# SH1_-_Connectors.net
KiCad netlist of a schematic drawn in Altium Designer
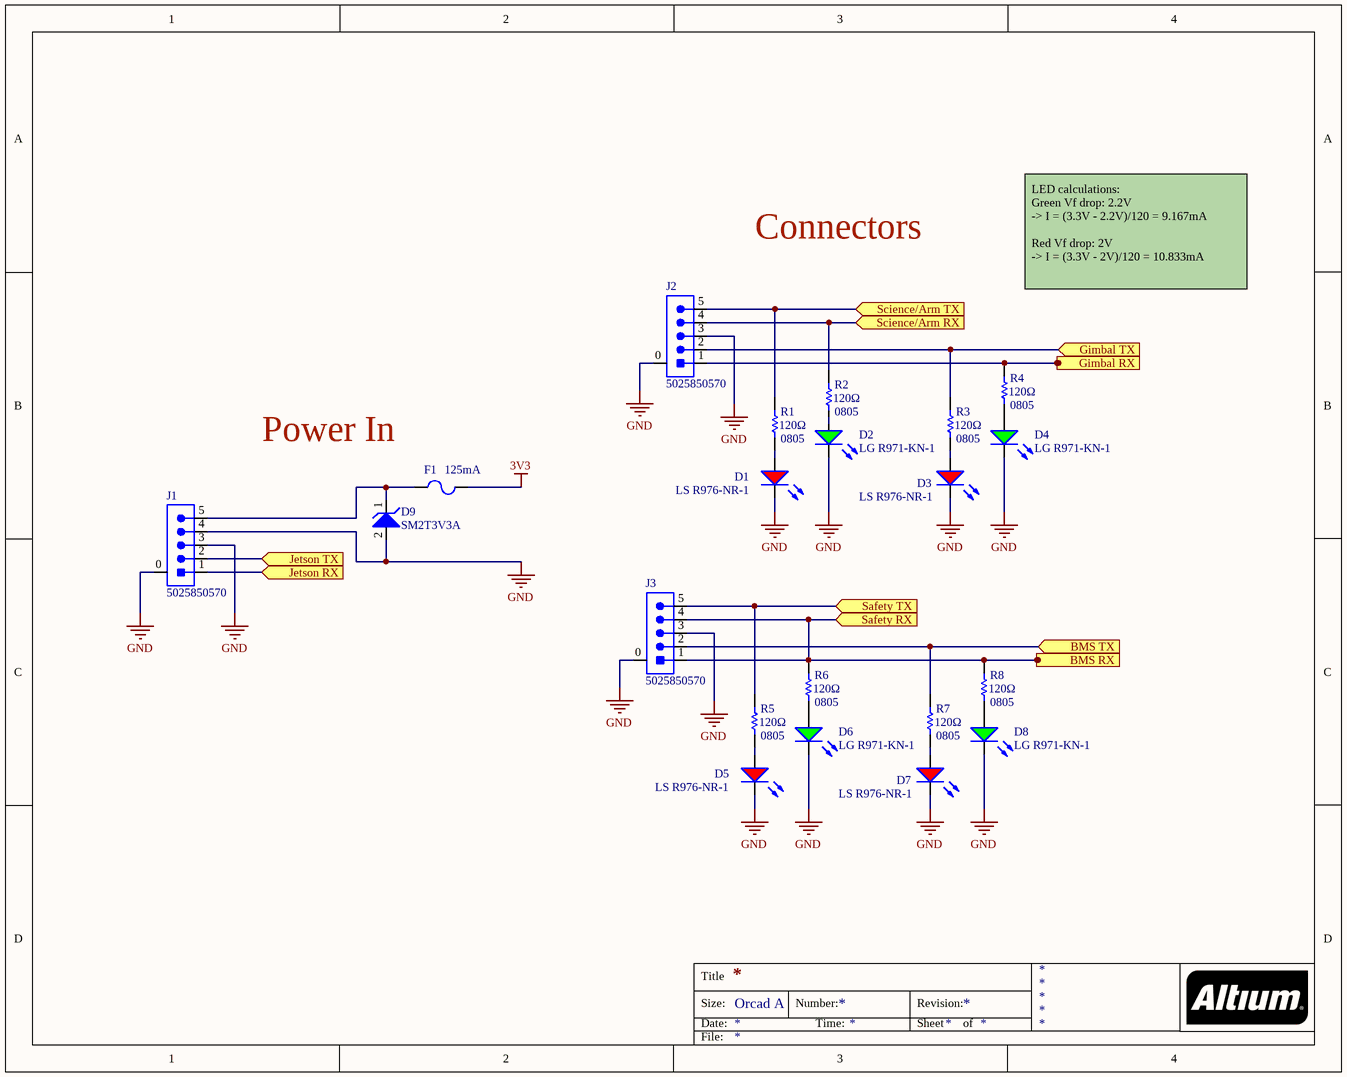
[diagram p0: SH1 - Connectors.SchDoc]

(export (version "E")
  (design (tool "Eeschema 10.0.6"))
  (components
    (comp (ref "D1")
      (value "LS R976-NR-1")
      (footprint "LED_0805_LINE")
      (description "LED RED DIFFUSED 0805 SMD")
      (fields (field (name "MANUFACTURER PART NUMBER 1") "LS R976-NR-1"))
      (libsource (lib "UWRT_Schematic_Library_2020") (part "DIO_LED_R"))
    )
    (comp (ref "D2")
      (value "LG R971-KN-1")
      (footprint "LED_0805_LINE")
      (description "LED GREEN DIFFUSED 0805 SMD")
      (fields (field (name "MANUFACTURER PART NUMBER 1") "LG R971-KN-1"))
      (libsource (lib "UWRT_Schematic_Library_2020") (part "DIO_LED_G"))
    )
    (comp (ref "D3")
      (value "LS R976-NR-1")
      (footprint "LED_0805_LINE")
      (description "LED RED DIFFUSED 0805 SMD")
      (fields (field (name "MANUFACTURER PART NUMBER 1") "LS R976-NR-1"))
      (libsource (lib "UWRT_Schematic_Library_2020") (part "DIO_LED_R"))
    )
    (comp (ref "D4")
      (value "LG R971-KN-1")
      (footprint "LED_0805_LINE")
      (description "LED GREEN DIFFUSED 0805 SMD")
      (fields (field (name "MANUFACTURER PART NUMBER 1") "LG R971-KN-1"))
      (libsource (lib "UWRT_Schematic_Library_2020") (part "DIO_LED_G"))
    )
    (comp (ref "D5")
      (value "LS R976-NR-1")
      (footprint "LED_0805_LINE")
      (description "LED RED DIFFUSED 0805 SMD")
      (fields (field (name "MANUFACTURER PART NUMBER 1") "LS R976-NR-1"))
      (libsource (lib "UWRT_Schematic_Library_2020") (part "DIO_LED_R"))
    )
    (comp (ref "D6")
      (value "LG R971-KN-1")
      (footprint "LED_0805_LINE")
      (description "LED GREEN DIFFUSED 0805 SMD")
      (fields (field (name "MANUFACTURER PART NUMBER 1") "LG R971-KN-1"))
      (libsource (lib "UWRT_Schematic_Library_2020") (part "DIO_LED_G"))
    )
    (comp (ref "D7")
      (value "LS R976-NR-1")
      (footprint "LED_0805_LINE")
      (description "LED RED DIFFUSED 0805 SMD")
      (fields (field (name "MANUFACTURER PART NUMBER 1") "LS R976-NR-1"))
      (libsource (lib "UWRT_Schematic_Library_2020") (part "DIO_LED_R"))
    )
    (comp (ref "D8")
      (value "LG R971-KN-1")
      (footprint "LED_0805_LINE")
      (description "LED GREEN DIFFUSED 0805 SMD")
      (fields (field (name "MANUFACTURER PART NUMBER 1") "LG R971-KN-1"))
      (libsource (lib "UWRT_Schematic_Library_2020") (part "DIO_LED_G"))
    )
    (comp (ref "D9")
      (value "TVS_DIODE_UNIDIR_3.3V")
      (footprint "TVS_DIODE_UNIDIR")
      (description "TVS DIODE 3.3V 6.8V DO216AA")
      (fields
        (field (name "MANUFACTURER") "STMicroelectronics")
        (field (name "MANUFACTURER PART NUMBER") "SM2T3V3A")
      )
      (libsource (lib "UWRT_Schematic_Library_2020") (part "TVS_DIODE_UNIDIR_3.3V"))
    )
    (comp (ref "F1")
      (value "FUSE_125mA_1206")
      (footprint "FUSE_1206")
      (description "FUSE SMD 125mA 125V")
      (fields (field (name "CURRENT RATING") "125mA"))
      (libsource (lib "UWRT_Schematic_Library_2020") (part "FUSE_125mA_1206"))
    )
    (comp (ref "J1")
      (value "CON_5M_SM_RA")
      (footprint "MOLEX-5025850570")
      (description "CONN HEADER SMD RIGHT ANGLE 1.5MM PITCH")
      (fields (field (name "MANUFACTURER PART NUMBER 1") "5025850570"))
      (libsource (lib "UWRT_Schematic_Library_2020") (part "CON_5M_SM_RA"))
    )
    (comp (ref "J2")
      (value "CON_5M_SM_RA")
      (footprint "MOLEX-5025850570")
      (description "CONN HEADER SMD RIGHT ANGLE 1.5MM PITCH")
      (fields (field (name "MANUFACTURER PART NUMBER 1") "5025850570"))
      (libsource (lib "UWRT_Schematic_Library_2020") (part "CON_5M_SM_RA"))
    )
    (comp (ref "J3")
      (value "CON_5M_SM_RA")
      (footprint "MOLEX-5025850570")
      (description "CONN HEADER SMD RIGHT ANGLE 1.5MM PITCH")
      (fields (field (name "MANUFACTURER PART NUMBER 1") "5025850570"))
      (libsource (lib "UWRT_Schematic_Library_2020") (part "CON_5M_SM_RA"))
    )
    (comp (ref "R1")
      (value "120")
      (footprint "RESC2012X60N")
      (description "RES SMD 120 OHM 1% 1/8W 0805")
      (fields (field (name "CASE CODE (IMPERIAL)") "0805") (field (name "RESISTANCE") "120Ω"))
      (libsource (lib "UWRT_Schematic_Library_2020") (part "RES_120Ω_0805"))
    )
    (comp (ref "R2")
      (value "120")
      (footprint "RESC2012X60N")
      (description "RES SMD 120 OHM 1% 1/8W 0805")
      (fields (field (name "CASE CODE (IMPERIAL)") "0805") (field (name "RESISTANCE") "120Ω"))
      (libsource (lib "UWRT_Schematic_Library_2020") (part "RES_120Ω_0805"))
    )
    (comp (ref "R3")
      (value "120")
      (footprint "RESC2012X60N")
      (description "RES SMD 120 OHM 1% 1/8W 0805")
      (fields (field (name "CASE CODE (IMPERIAL)") "0805") (field (name "RESISTANCE") "120Ω"))
      (libsource (lib "UWRT_Schematic_Library_2020") (part "RES_120Ω_0805"))
    )
    (comp (ref "R4")
      (value "120")
      (footprint "RESC2012X60N")
      (description "RES SMD 120 OHM 1% 1/8W 0805")
      (fields (field (name "CASE CODE (IMPERIAL)") "0805") (field (name "RESISTANCE") "120Ω"))
      (libsource (lib "UWRT_Schematic_Library_2020") (part "RES_120Ω_0805"))
    )
    (comp (ref "R5")
      (value "120")
      (footprint "RESC2012X60N")
      (description "RES SMD 120 OHM 1% 1/8W 0805")
      (fields (field (name "CASE CODE (IMPERIAL)") "0805") (field (name "RESISTANCE") "120Ω"))
      (libsource (lib "UWRT_Schematic_Library_2020") (part "RES_120Ω_0805"))
    )
    (comp (ref "R6")
      (value "120")
      (footprint "RESC2012X60N")
      (description "RES SMD 120 OHM 1% 1/8W 0805")
      (fields (field (name "CASE CODE (IMPERIAL)") "0805") (field (name "RESISTANCE") "120Ω"))
      (libsource (lib "UWRT_Schematic_Library_2020") (part "RES_120Ω_0805"))
    )
    (comp (ref "R7")
      (value "120")
      (footprint "RESC2012X60N")
      (description "RES SMD 120 OHM 1% 1/8W 0805")
      (fields (field (name "CASE CODE (IMPERIAL)") "0805") (field (name "RESISTANCE") "120Ω"))
      (libsource (lib "UWRT_Schematic_Library_2020") (part "RES_120Ω_0805"))
    )
    (comp (ref "R8")
      (value "120")
      (footprint "RESC2012X60N")
      (description "RES SMD 120 OHM 1% 1/8W 0805")
      (fields (field (name "CASE CODE (IMPERIAL)") "0805") (field (name "RESISTANCE") "120Ω"))
      (libsource (lib "UWRT_Schematic_Library_2020") (part "RES_120Ω_0805"))
    )
  )
  (nets
    (net (code "1") (name "/BMS RX") (class "Default")
      (node (ref "J3") (pin "1") (pinfunction "1_1") (pintype "passive"))
      (node (ref "J3") (pin "4") (pinfunction "4_4") (pintype "passive"))
      (node (ref "R6") (pin "1") (pinfunction "1_1") (pintype "passive"))
      (node (ref "R8") (pin "1") (pinfunction "1_1") (pintype "passive"))
    )
    (net (code "2") (name "/BMS TX") (class "Default")
      (node (ref "J3") (pin "2") (pinfunction "2_2") (pintype "passive"))
      (node (ref "R7") (pin "1") (pinfunction "1_1") (pintype "passive"))
    )
    (net (code "3") (name "/Gimbal RX") (class "Default")
      (node (ref "J2") (pin "1") (pinfunction "1_1") (pintype "passive"))
      (node (ref "R4") (pin "1") (pinfunction "1_1") (pintype "passive"))
    )
    (net (code "4") (name "/Gimbal TX") (class "Default")
      (node (ref "J2") (pin "2") (pinfunction "2_2") (pintype "passive"))
      (node (ref "R3") (pin "1") (pinfunction "1_1") (pintype "passive"))
    )
    (net (code "5") (name "/Jetson RX") (class "Default")
      (node (ref "J1") (pin "1") (pinfunction "1_1") (pintype "passive"))
    )
    (net (code "6") (name "/Jetson TX") (class "Default")
      (node (ref "J1") (pin "2") (pinfunction "2_2") (pintype "passive"))
    )
    (net (code "7") (name "/Safety TX") (class "Default")
      (node (ref "J3") (pin "5") (pinfunction "5_5") (pintype "passive"))
      (node (ref "R5") (pin "1") (pinfunction "1_1") (pintype "passive"))
    )
    (net (code "8") (name "/Science{slash}Arm RX") (class "Default")
      (node (ref "J2") (pin "4") (pinfunction "4_4") (pintype "passive"))
      (node (ref "R2") (pin "1") (pinfunction "1_1") (pintype "passive"))
    )
    (net (code "9") (name "/Science{slash}Arm TX") (class "Default")
      (node (ref "J2") (pin "5") (pinfunction "5_5") (pintype "passive"))
      (node (ref "R1") (pin "1") (pinfunction "1_1") (pintype "passive"))
    )
    (net (code "10") (name "3V3") (class "Default")
      (node (ref "F1") (pin "2") (pinfunction "2_2") (pintype "passive"))
    )
    (net (code "11") (name "GND") (class "Default")
      (node (ref "D1") (pin "2") (pinfunction "K_2") (pintype "passive"))
      (node (ref "D2") (pin "2") (pinfunction "K_2") (pintype "passive"))
      (node (ref "D3") (pin "2") (pinfunction "K_2") (pintype "passive"))
      (node (ref "D4") (pin "2") (pinfunction "K_2") (pintype "passive"))
      (node (ref "D5") (pin "2") (pinfunction "K_2") (pintype "passive"))
      (node (ref "D6") (pin "2") (pinfunction "K_2") (pintype "passive"))
      (node (ref "D7") (pin "2") (pinfunction "K_2") (pintype "passive"))
      (node (ref "D8") (pin "2") (pinfunction "K_2") (pintype "passive"))
      (node (ref "D9") (pin "2") (pinfunction "2_2") (pintype "passive"))
      (node (ref "J1") (pin "0") (pinfunction "0_0") (pintype "passive"))
      (node (ref "J1") (pin "3") (pinfunction "3_3") (pintype "passive"))
      (node (ref "J1") (pin "4") (pinfunction "4_4") (pintype "passive"))
      (node (ref "J2") (pin "0") (pinfunction "0_0") (pintype "passive"))
      (node (ref "J2") (pin "3") (pinfunction "3_3") (pintype "passive"))
      (node (ref "J3") (pin "0") (pinfunction "0_0") (pintype "passive"))
      (node (ref "J3") (pin "3") (pinfunction "3_3") (pintype "passive"))
    )
    (net (code "12") (name "Net-(D1-A)") (class "Default")
      (node (ref "D1") (pin "1") (pinfunction "A_1") (pintype "passive"))
      (node (ref "R1") (pin "2") (pinfunction "2_2") (pintype "passive"))
    )
    (net (code "13") (name "Net-(D2-A)") (class "Default")
      (node (ref "D2") (pin "1") (pinfunction "A_1") (pintype "passive"))
      (node (ref "R2") (pin "2") (pinfunction "2_2") (pintype "passive"))
    )
    (net (code "14") (name "Net-(D3-A)") (class "Default")
      (node (ref "D3") (pin "1") (pinfunction "A_1") (pintype "passive"))
      (node (ref "R3") (pin "2") (pinfunction "2_2") (pintype "passive"))
    )
    (net (code "15") (name "Net-(D4-A)") (class "Default")
      (node (ref "D4") (pin "1") (pinfunction "A_1") (pintype "passive"))
      (node (ref "R4") (pin "2") (pinfunction "2_2") (pintype "passive"))
    )
    (net (code "16") (name "Net-(D5-A)") (class "Default")
      (node (ref "D5") (pin "1") (pinfunction "A_1") (pintype "passive"))
      (node (ref "R5") (pin "2") (pinfunction "2_2") (pintype "passive"))
    )
    (net (code "17") (name "Net-(D6-A)") (class "Default")
      (node (ref "D6") (pin "1") (pinfunction "A_1") (pintype "passive"))
      (node (ref "R6") (pin "2") (pinfunction "2_2") (pintype "passive"))
    )
    (net (code "18") (name "Net-(D7-A)") (class "Default")
      (node (ref "D7") (pin "1") (pinfunction "A_1") (pintype "passive"))
      (node (ref "R7") (pin "2") (pinfunction "2_2") (pintype "passive"))
    )
    (net (code "19") (name "Net-(D8-A)") (class "Default")
      (node (ref "D8") (pin "1") (pinfunction "A_1") (pintype "passive"))
      (node (ref "R8") (pin "2") (pinfunction "2_2") (pintype "passive"))
    )
    (net (code "20") (name "Net-(D9-Pad1)") (class "Default")
      (node (ref "D9") (pin "1") (pinfunction "1_1") (pintype "passive"))
      (node (ref "F1") (pin "1") (pinfunction "1_1") (pintype "passive"))
      (node (ref "J1") (pin "5") (pinfunction "5_5") (pintype "passive"))
    )
  )
)
